# DroidController_rev02.net
KiCad netlist of a schematic drawn in EAGLE
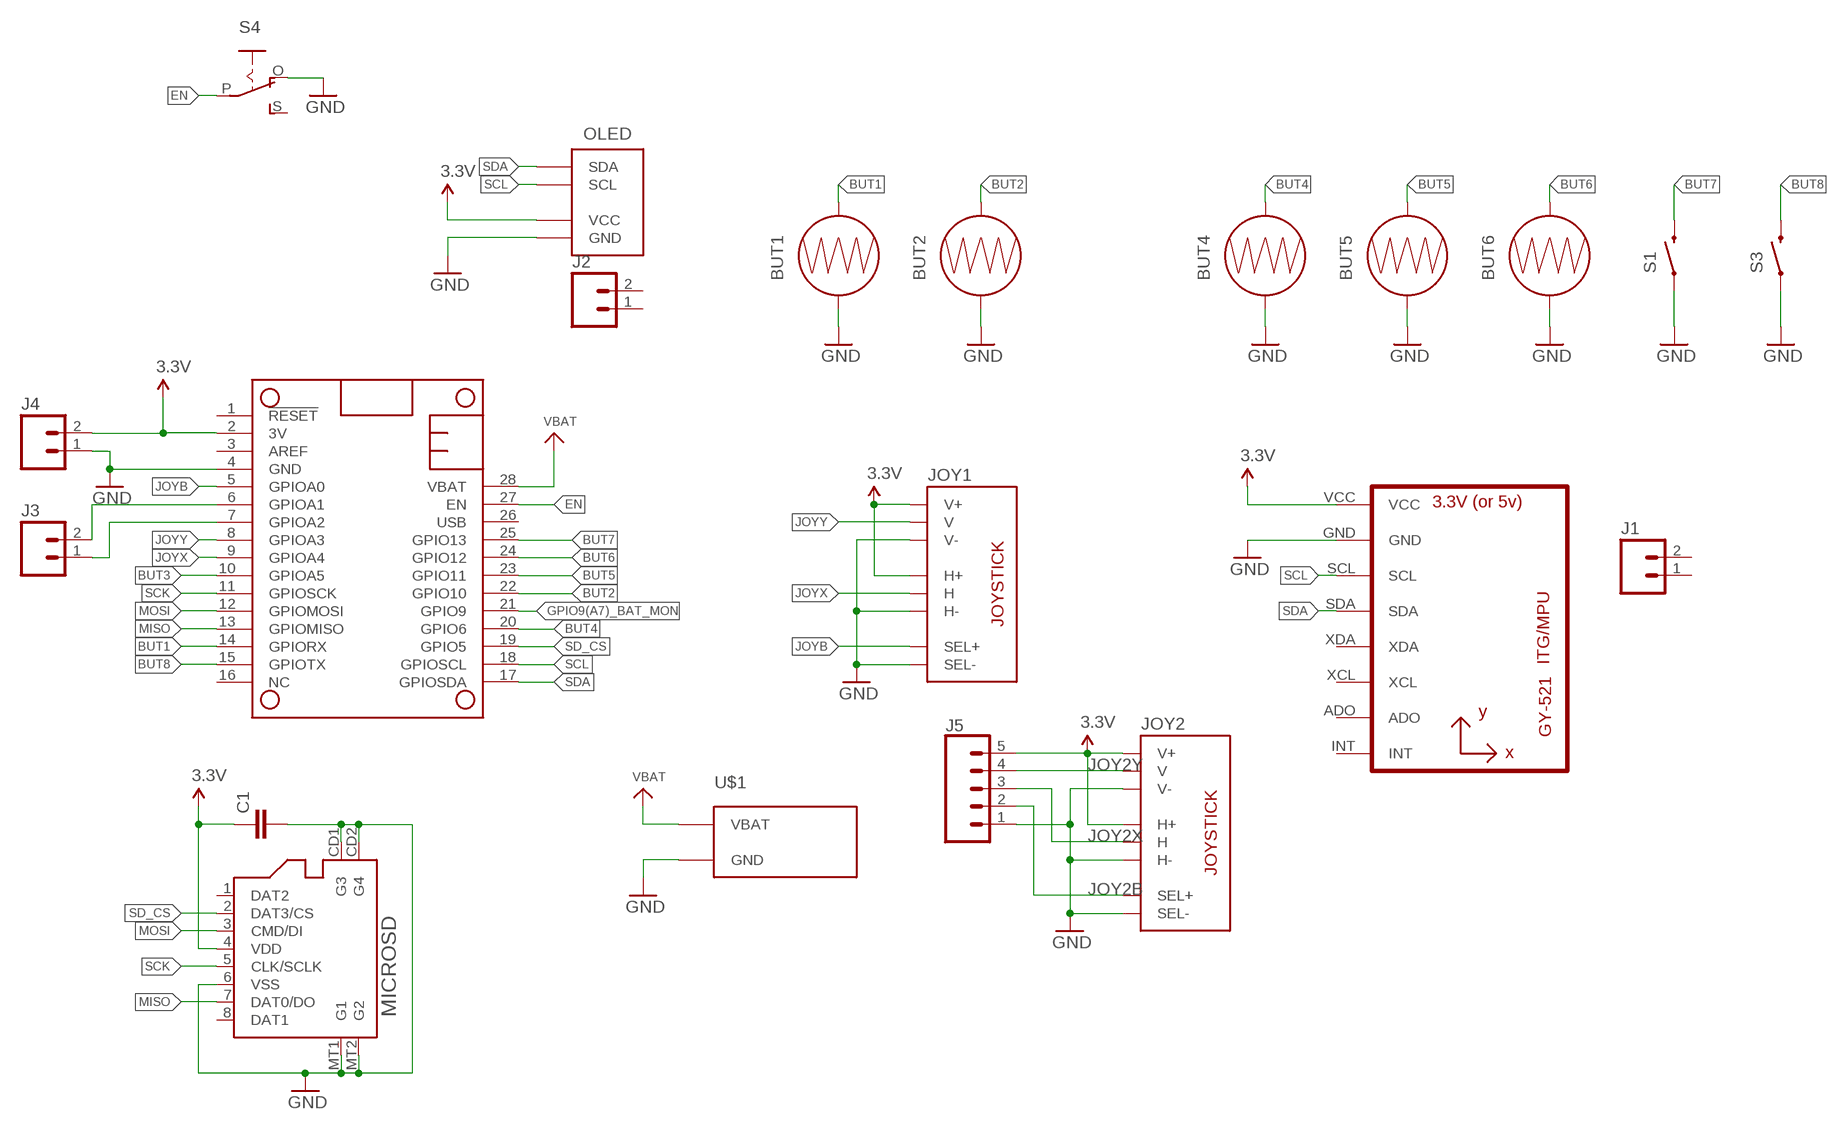
[diagram p0: schematic, sheet 1]

(export (version "E")
  (design (tool "Eeschema 10.0.6"))
  (components
    (comp (ref "BUT1")
      (value "BUTTON-CONDUCTIVEBUTTON-COND2")
      (footprint "eagle-import:BUTTON-CONDUCTIVE2")
      (libsource (lib "eagle-import") (part "BUTTON-CONDUCTIVEBUTTON-COND2"))
    )
    (comp (ref "BUT2")
      (value "BUTTON-CONDUCTIVEBUTTON-COND2")
      (footprint "eagle-import:BUTTON-CONDUCTIVE2")
      (libsource (lib "eagle-import") (part "BUTTON-CONDUCTIVEBUTTON-COND2"))
    )
    (comp (ref "BUT4")
      (value "BUTTON-CONDUCTIVEBUTTON-COND2")
      (footprint "eagle-import:BUTTON-CONDUCTIVE2")
      (libsource (lib "eagle-import") (part "BUTTON-CONDUCTIVEBUTTON-COND2"))
    )
    (comp (ref "BUT5")
      (value "BUTTON-CONDUCTIVEBUTTON-COND2")
      (footprint "eagle-import:BUTTON-CONDUCTIVE2")
      (libsource (lib "eagle-import") (part "BUTTON-CONDUCTIVEBUTTON-COND2"))
    )
    (comp (ref "BUT6")
      (value "BUTTON-CONDUCTIVEBUTTON-COND2")
      (footprint "eagle-import:BUTTON-CONDUCTIVE2")
      (libsource (lib "eagle-import") (part "BUTTON-CONDUCTIVEBUTTON-COND2"))
    )
    (comp (ref "C1")
      (value "C-EUC0603")
      (footprint "eagle-import:C0603")
      (libsource (lib "eagle-import") (part "C-EUC0603"))
    )
    (comp (ref "J1")
      (value "M02PTH")
      (footprint "eagle-import:1X02")
      (libsource (lib "eagle-import") (part "M02PTH"))
    )
    (comp (ref "J2")
      (value "M02PTH")
      (footprint "eagle-import:1X02")
      (libsource (lib "eagle-import") (part "M02PTH"))
    )
    (comp (ref "J3")
      (value "M02PTH")
      (footprint "eagle-import:1X02")
      (libsource (lib "eagle-import") (part "M02PTH"))
    )
    (comp (ref "J4")
      (value "M02PTH")
      (footprint "eagle-import:1X02")
      (libsource (lib "eagle-import") (part "M02PTH"))
    )
    (comp (ref "J5")
      (value "CONN_05")
      (footprint "eagle-import:1X05")
      (libsource (lib "eagle-import") (part "CONN_05"))
    )
    (comp (ref "JOY1")
      (value "JOYSTICK")
      (footprint "eagle-import:JOYSTICK_SM")
      (libsource (lib "eagle-import") (part "JOYSTICK"))
    )
    (comp (ref "JOY2")
      (value "JOYSTICK")
      (footprint "eagle-import:JOYSTICK_SM")
      (libsource (lib "eagle-import") (part "JOYSTICK"))
    )
    (comp (ref "MICROSD")
      (value "MICROSD")
      (footprint "eagle-import:MICROSD_SMALL")
      (libsource (lib "eagle-import") (part "MICROSD"))
    )
    (comp (ref "MS1")
      (value "FEATHERWING_NODIM")
      (footprint "eagle-import:FEATHERWING_DIM")
      (libsource (lib "eagle-import") (part "FEATHERWING_NODIM"))
    )
    (comp (ref "OLED")
      (value "SH1106_I2C")
      (footprint "eagle-import:SH1106_128X32")
      (libsource (lib "eagle-import") (part "SH1106_I2C"))
    )
    (comp (ref "S1")
      (value "SWITCH-MOMENTARY-2SIDE_EZ")
      (footprint "eagle-import:TACTILE-PTH-SIDEEZ")
      (libsource (lib "eagle-import") (part "SWITCH-MOMENTARY-2SIDE_EZ"))
    )
    (comp (ref "S3")
      (value "SWITCH-MOMENTARY-2SIDE_EZ")
      (footprint "eagle-import:TACTILE-PTH-SIDEEZ")
      (libsource (lib "eagle-import") (part "SWITCH-MOMENTARY-2SIDE_EZ"))
    )
    (comp (ref "S4")
      (value "EG1218S")
      (footprint "eagle-import:EG1218")
      (libsource (lib "eagle-import") (part "EG1218S"))
    )
    (comp (ref "U$1")
      (value "KEYSTONE_BAT")
      (footprint "eagle-import:1042")
      (libsource (lib "eagle-import") (part "KEYSTONE_BAT"))
    )
    (comp (ref "U2")
      (value "GY-521MPU6050")
      (footprint "eagle-import:GY-521")
      (libsource (lib "eagle-import") (part "GY-521MPU6050"))
    )
  )
  (nets
    (net (code "1") (name "/JOY2B") (class "Default")
      (node (ref "J5") (pin "2") (pinfunction "2_2") (pintype "passive"))
      (node (ref "JOY2") (pin "B1A") (pinfunction "SEL+_B1A") (pintype "bidirectional"))
    )
    (net (code "2") (name "/JOY2X") (class "Default")
      (node (ref "J5") (pin "3") (pinfunction "3_3") (pintype "passive"))
      (node (ref "JOY2") (pin "H2") (pinfunction "H_H2") (pintype "bidirectional"))
    )
    (net (code "3") (name "/JOY2Y") (class "Default")
      (node (ref "J5") (pin "4") (pinfunction "4_4") (pintype "passive"))
      (node (ref "JOY2") (pin "V2") (pinfunction "V_V2") (pintype "bidirectional"))
    )
    (net (code "4") (name "/USB") (class "Default")
      (node (ref "MS1") (pin "26") (pinfunction "USB_26") (pintype "power_in"))
    )
    (net (code "5") (name "3.3V") (class "Default")
      (node (ref "C1") (pin "1") (pinfunction "1_1") (pintype "passive"))
      (node (ref "J4") (pin "2") (pinfunction "2_2") (pintype "passive"))
      (node (ref "J5") (pin "5") (pinfunction "5_5") (pintype "passive"))
      (node (ref "JOY1") (pin "H1") (pinfunction "H+_H1") (pintype "bidirectional"))
      (node (ref "JOY1") (pin "V1") (pinfunction "V+_V1") (pintype "bidirectional"))
      (node (ref "JOY2") (pin "H1") (pinfunction "H+_H1") (pintype "bidirectional"))
      (node (ref "JOY2") (pin "V1") (pinfunction "V+_V1") (pintype "bidirectional"))
      (node (ref "MICROSD") (pin "4") (pinfunction "VDD_4") (pintype "power_in"))
      (node (ref "MS1") (pin "2") (pinfunction "3V_2") (pintype "power_in"))
      (node (ref "OLED") (pin "VCC") (pinfunction "VCC_VCC") (pintype "bidirectional"))
      (node (ref "U2") (pin "VCC") (pinfunction "VCC_VCC") (pintype "bidirectional"))
    )
    (net (code "6") (name "BUT1") (class "Default")
      (node (ref "BUT1") (pin "2") (pinfunction "2_2") (pintype "passive"))
      (node (ref "MS1") (pin "14") (pinfunction "GPIORX_14") (pintype "bidirectional"))
    )
    (net (code "7") (name "BUT2") (class "Default")
      (node (ref "BUT2") (pin "2") (pinfunction "2_2") (pintype "passive"))
      (node (ref "MS1") (pin "22") (pinfunction "GPIO10_22") (pintype "bidirectional"))
    )
    (net (code "8") (name "BUT3") (class "Default")
      (node (ref "MS1") (pin "10") (pinfunction "GPIOA5_10") (pintype "bidirectional"))
    )
    (net (code "9") (name "BUT4") (class "Default")
      (node (ref "BUT4") (pin "2") (pinfunction "2_2") (pintype "passive"))
      (node (ref "MS1") (pin "20") (pinfunction "GPIO6_20") (pintype "bidirectional"))
    )
    (net (code "10") (name "BUT5") (class "Default")
      (node (ref "BUT5") (pin "2") (pinfunction "2_2") (pintype "passive"))
      (node (ref "MS1") (pin "23") (pinfunction "GPIO11_23") (pintype "bidirectional"))
    )
    (net (code "11") (name "BUT6") (class "Default")
      (node (ref "BUT6") (pin "2") (pinfunction "2_2") (pintype "passive"))
      (node (ref "MS1") (pin "24") (pinfunction "GPIO12_24") (pintype "bidirectional"))
    )
    (net (code "12") (name "BUT7") (class "Default")
      (node (ref "MS1") (pin "25") (pinfunction "GPIO13_25") (pintype "bidirectional"))
      (node (ref "S1") (pin "2") (pinfunction "2_2") (pintype "passive"))
    )
    (net (code "13") (name "BUT8") (class "Default")
      (node (ref "MS1") (pin "15") (pinfunction "GPIOTX_15") (pintype "bidirectional"))
      (node (ref "S3") (pin "2") (pinfunction "2_2") (pintype "passive"))
    )
    (net (code "14") (name "EN") (class "Default")
      (node (ref "MS1") (pin "27") (pinfunction "EN_27") (pintype "passive"))
      (node (ref "S4") (pin "P") (pinfunction "P_P") (pintype "passive"))
    )
    (net (code "15") (name "GND") (class "Default")
      (node (ref "BUT1") (pin "1") (pinfunction "1_1") (pintype "passive"))
      (node (ref "BUT2") (pin "1") (pinfunction "1_1") (pintype "passive"))
      (node (ref "BUT4") (pin "1") (pinfunction "1_1") (pintype "passive"))
      (node (ref "BUT5") (pin "1") (pinfunction "1_1") (pintype "passive"))
      (node (ref "BUT6") (pin "1") (pinfunction "1_1") (pintype "passive"))
      (node (ref "C1") (pin "2") (pinfunction "2_2") (pintype "passive"))
      (node (ref "J4") (pin "1") (pinfunction "1_1") (pintype "passive"))
      (node (ref "J5") (pin "1") (pinfunction "1_1") (pintype "passive"))
      (node (ref "JOY1") (pin "B2A") (pinfunction "SEL-_B2A") (pintype "bidirectional"))
      (node (ref "JOY1") (pin "H3") (pinfunction "H-_H3") (pintype "bidirectional"))
      (node (ref "JOY1") (pin "V3") (pinfunction "V-_V3") (pintype "bidirectional"))
      (node (ref "JOY2") (pin "B2A") (pinfunction "SEL-_B2A") (pintype "bidirectional"))
      (node (ref "JOY2") (pin "H3") (pinfunction "H-_H3") (pintype "bidirectional"))
      (node (ref "JOY2") (pin "V3") (pinfunction "V-_V3") (pintype "bidirectional"))
      (node (ref "MICROSD") (pin "6") (pinfunction "VSS_6") (pintype "power_in"))
      (node (ref "MICROSD") (pin "CD1") (pinfunction "G3_CD1") (pintype "passive"))
      (node (ref "MICROSD") (pin "CD2") (pinfunction "G4_CD2") (pintype "passive"))
      (node (ref "MICROSD") (pin "MT1") (pinfunction "G1_MT1") (pintype "power_in"))
      (node (ref "MICROSD") (pin "MT2") (pinfunction "G2_MT2") (pintype "power_in"))
      (node (ref "MS1") (pin "4") (pinfunction "GND_4") (pintype "power_in"))
      (node (ref "OLED") (pin "GND") (pinfunction "GND_GND") (pintype "bidirectional"))
      (node (ref "S1") (pin "1") (pinfunction "1_1") (pintype "passive"))
      (node (ref "S3") (pin "1") (pinfunction "1_1") (pintype "passive"))
      (node (ref "S4") (pin "O") (pinfunction "O_O") (pintype "passive"))
      (node (ref "U$1") (pin "GND") (pinfunction "GND_GND") (pintype "bidirectional"))
      (node (ref "U2") (pin "GND") (pinfunction "GND_GND") (pintype "bidirectional"))
    )
    (net (code "16") (name "GPIO9(A7)_BAT_MON") (class "Default")
      (node (ref "MS1") (pin "21") (pinfunction "GPIO9_21") (pintype "bidirectional"))
    )
    (net (code "17") (name "JOYB") (class "Default")
      (node (ref "JOY1") (pin "B1A") (pinfunction "SEL+_B1A") (pintype "bidirectional"))
      (node (ref "MS1") (pin "5") (pinfunction "GPIOA0_5") (pintype "bidirectional"))
    )
    (net (code "18") (name "JOYX") (class "Default")
      (node (ref "JOY1") (pin "H2") (pinfunction "H_H2") (pintype "bidirectional"))
      (node (ref "MS1") (pin "9") (pinfunction "GPIOA4_9") (pintype "bidirectional"))
    )
    (net (code "19") (name "JOYY") (class "Default")
      (node (ref "JOY1") (pin "V2") (pinfunction "V_V2") (pintype "bidirectional"))
      (node (ref "MS1") (pin "8") (pinfunction "GPIOA3_8") (pintype "bidirectional"))
    )
    (net (code "20") (name "MISO") (class "Default")
      (node (ref "MICROSD") (pin "7") (pinfunction "DAT0/DO_7") (pintype "output"))
      (node (ref "MS1") (pin "13") (pinfunction "GPIOMISO_13") (pintype "bidirectional"))
    )
    (net (code "21") (name "MOSI") (class "Default")
      (node (ref "MICROSD") (pin "3") (pinfunction "CMD/DI_3") (pintype "input"))
      (node (ref "MS1") (pin "12") (pinfunction "GPIOMOSI_12") (pintype "bidirectional"))
    )
    (net (code "22") (name "Net-(MS1-GPIOA1)") (class "Default")
      (node (ref "J3") (pin "2") (pinfunction "2_2") (pintype "passive"))
      (node (ref "MS1") (pin "6") (pinfunction "GPIOA1_6") (pintype "bidirectional"))
    )
    (net (code "23") (name "Net-(MS1-GPIOA2)") (class "Default")
      (node (ref "J3") (pin "1") (pinfunction "1_1") (pintype "passive"))
      (node (ref "MS1") (pin "7") (pinfunction "GPIOA2_7") (pintype "bidirectional"))
    )
    (net (code "24") (name "SCK") (class "Default")
      (node (ref "MICROSD") (pin "5") (pinfunction "CLK/SCLK_5") (pintype "input"))
      (node (ref "MS1") (pin "11") (pinfunction "GPIOSCK_11") (pintype "bidirectional"))
    )
    (net (code "25") (name "SCL") (class "Default")
      (node (ref "MS1") (pin "18") (pinfunction "GPIOSCL_18") (pintype "bidirectional"))
      (node (ref "OLED") (pin "SCL") (pinfunction "SCL_SCL") (pintype "bidirectional"))
      (node (ref "U2") (pin "SCL") (pinfunction "SCL_SCL") (pintype "bidirectional"))
    )
    (net (code "26") (name "SDA") (class "Default")
      (node (ref "MS1") (pin "17") (pinfunction "GPIOSDA_17") (pintype "bidirectional"))
      (node (ref "OLED") (pin "SDA") (pinfunction "SDA_SDA") (pintype "bidirectional"))
      (node (ref "U2") (pin "SDA") (pinfunction "SDA_SDA") (pintype "bidirectional"))
    )
    (net (code "27") (name "SD_CS") (class "Default")
      (node (ref "MICROSD") (pin "2") (pinfunction "DAT3/CS_2") (pintype "input"))
      (node (ref "MS1") (pin "19") (pinfunction "GPIO5_19") (pintype "bidirectional"))
    )
    (net (code "28") (name "VBAT") (class "Default")
      (node (ref "MS1") (pin "28") (pinfunction "VBAT_28") (pintype "power_in"))
      (node (ref "U$1") (pin "VBAT") (pinfunction "VBAT_VBAT") (pintype "bidirectional"))
    )
    (net (code "29") (name "unconnected-(J1-Pad1)") (class "Default")
      (node (ref "J1") (pin "1") (pinfunction "1_1") (pintype "passive"))
    )
    (net (code "30") (name "unconnected-(J1-Pad2)") (class "Default")
      (node (ref "J1") (pin "2") (pinfunction "2_2") (pintype "passive"))
    )
    (net (code "31") (name "unconnected-(J2-Pad1)") (class "Default")
      (node (ref "J2") (pin "1") (pinfunction "1_1") (pintype "passive"))
    )
    (net (code "32") (name "unconnected-(J2-Pad2)") (class "Default")
      (node (ref "J2") (pin "2") (pinfunction "2_2") (pintype "passive"))
    )
    (net (code "33") (name "unconnected-(MICROSD-DAT1-Pad8)") (class "Default")
      (node (ref "MICROSD") (pin "8") (pinfunction "DAT1_8") (pintype "bidirectional"))
    )
    (net (code "34") (name "unconnected-(MICROSD-DAT2-Pad1)") (class "Default")
      (node (ref "MICROSD") (pin "1") (pinfunction "DAT2_1") (pintype "bidirectional"))
    )
    (net (code "35") (name "unconnected-(MS1-AREF-Pad3)") (class "Default")
      (node (ref "MS1") (pin "3") (pinfunction "AREF_3") (pintype "passive"))
    )
    (net (code "36") (name "unconnected-(MS1-NC-Pad16)") (class "Default")
      (node (ref "MS1") (pin "16") (pinfunction "NC_16") (pintype "passive"))
    )
    (net (code "37") (name "unconnected-(MS1-~{RESET}-Pad1)") (class "Default")
      (node (ref "MS1") (pin "1") (pinfunction "~{RESET}_1") (pintype "input"))
    )
    (net (code "38") (name "unconnected-(S4-PadS)") (class "Default")
      (node (ref "S4") (pin "S") (pinfunction "S_S") (pintype "passive"))
    )
    (net (code "39") (name "unconnected-(U2-PadADO)") (class "Default")
      (node (ref "U2") (pin "ADO") (pinfunction "ADO_ADO") (pintype "bidirectional"))
    )
    (net (code "40") (name "unconnected-(U2-PadINT)") (class "Default")
      (node (ref "U2") (pin "INT") (pinfunction "INT_INT") (pintype "bidirectional"))
    )
    (net (code "41") (name "unconnected-(U2-PadXCL)") (class "Default")
      (node (ref "U2") (pin "XCL") (pinfunction "XCL_XCL") (pintype "bidirectional"))
    )
    (net (code "42") (name "unconnected-(U2-PadXDA)") (class "Default")
      (node (ref "U2") (pin "XDA") (pinfunction "XDA_XDA") (pintype "bidirectional"))
    )
  )
)
